# MainBoard.net
KiCad netlist of a schematic drawn in EAGLE
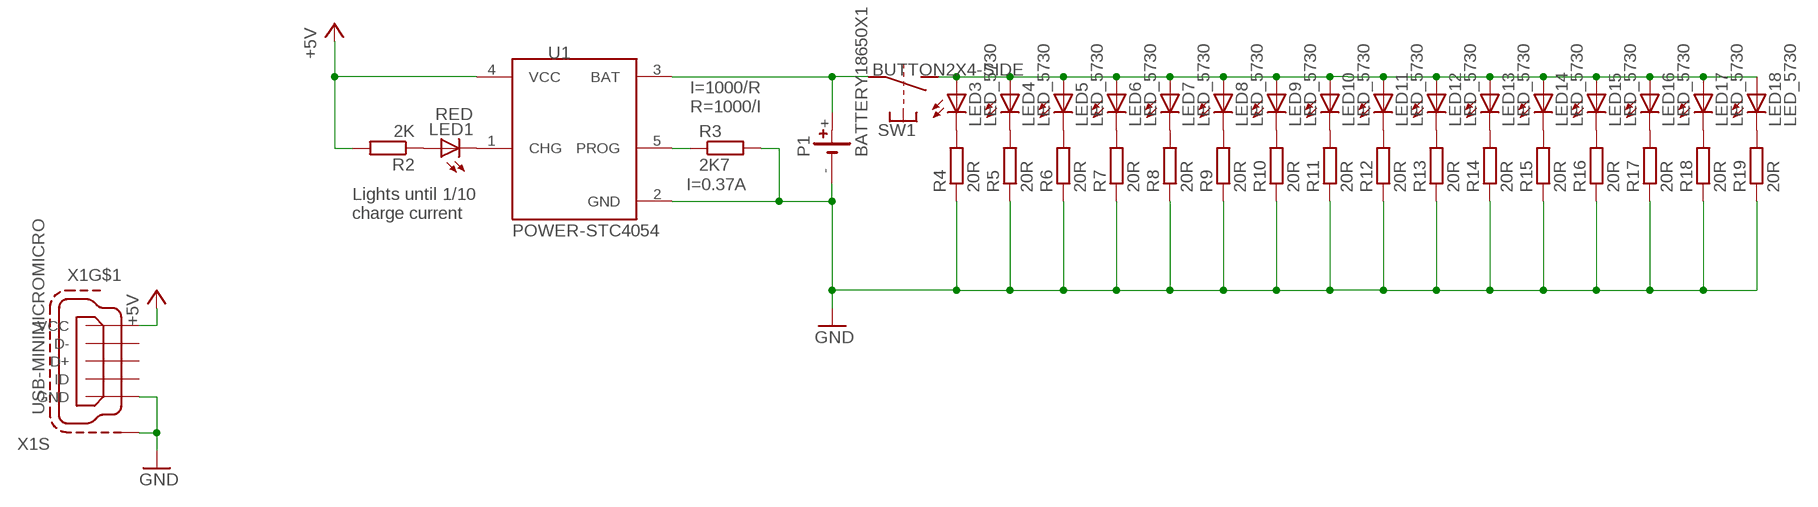
[diagram p0: schematic, sheet 1]

(export (version "E")
  (design (tool "Eeschema 10.0.6"))
  (components
    (comp (ref "LED1")
      (value "RED")
      (footprint "eagle-import:LED1206")
      (libsource (lib "eagle-import") (part "LED_1206"))
    )
    (comp (ref "LED3")
      (value "LED_5730")
      (footprint "eagle-import:LED5730")
      (libsource (lib "eagle-import") (part "LED_5730"))
    )
    (comp (ref "LED4")
      (value "LED_5730")
      (footprint "eagle-import:LED5730")
      (libsource (lib "eagle-import") (part "LED_5730"))
    )
    (comp (ref "LED5")
      (value "LED_5730")
      (footprint "eagle-import:LED5730")
      (libsource (lib "eagle-import") (part "LED_5730"))
    )
    (comp (ref "LED6")
      (value "LED_5730")
      (footprint "eagle-import:LED5730")
      (libsource (lib "eagle-import") (part "LED_5730"))
    )
    (comp (ref "LED7")
      (value "LED_5730")
      (footprint "eagle-import:LED5730")
      (libsource (lib "eagle-import") (part "LED_5730"))
    )
    (comp (ref "LED8")
      (value "LED_5730")
      (footprint "eagle-import:LED5730")
      (libsource (lib "eagle-import") (part "LED_5730"))
    )
    (comp (ref "LED9")
      (value "LED_5730")
      (footprint "eagle-import:LED5730")
      (libsource (lib "eagle-import") (part "LED_5730"))
    )
    (comp (ref "LED10")
      (value "LED_5730")
      (footprint "eagle-import:LED5730")
      (libsource (lib "eagle-import") (part "LED_5730"))
    )
    (comp (ref "LED11")
      (value "LED_5730")
      (footprint "eagle-import:LED5730")
      (libsource (lib "eagle-import") (part "LED_5730"))
    )
    (comp (ref "LED12")
      (value "LED_5730")
      (footprint "eagle-import:LED5730")
      (libsource (lib "eagle-import") (part "LED_5730"))
    )
    (comp (ref "LED13")
      (value "LED_5730")
      (footprint "eagle-import:LED5730")
      (libsource (lib "eagle-import") (part "LED_5730"))
    )
    (comp (ref "LED14")
      (value "LED_5730")
      (footprint "eagle-import:LED5730")
      (libsource (lib "eagle-import") (part "LED_5730"))
    )
    (comp (ref "LED15")
      (value "LED_5730")
      (footprint "eagle-import:LED5730")
      (libsource (lib "eagle-import") (part "LED_5730"))
    )
    (comp (ref "LED16")
      (value "LED_5730")
      (footprint "eagle-import:LED5730")
      (libsource (lib "eagle-import") (part "LED_5730"))
    )
    (comp (ref "LED17")
      (value "LED_5730")
      (footprint "eagle-import:LED5730")
      (libsource (lib "eagle-import") (part "LED_5730"))
    )
    (comp (ref "LED18")
      (value "LED_5730")
      (footprint "eagle-import:LED5730")
      (libsource (lib "eagle-import") (part "LED_5730"))
    )
    (comp (ref "P1")
      (value "BATTERY18650X1")
      (footprint "eagle-import:18650X1_HOLDER")
      (libsource (lib "eagle-import") (part "BATTERY18650X1"))
    )
    (comp (ref "R2")
      (value "2K")
      (footprint "eagle-import:RESC2012X50")
      (libsource (lib "eagle-import") (part "R_R0805"))
    )
    (comp (ref "R3")
      (value "2K7")
      (footprint "eagle-import:RESC2012X50")
      (libsource (lib "eagle-import") (part "R_R0805"))
    )
    (comp (ref "R4")
      (value "20R")
      (footprint "eagle-import:RESC2012X50")
      (libsource (lib "eagle-import") (part "R_R0805"))
    )
    (comp (ref "R5")
      (value "20R")
      (footprint "eagle-import:RESC2012X50")
      (libsource (lib "eagle-import") (part "R_R0805"))
    )
    (comp (ref "R6")
      (value "20R")
      (footprint "eagle-import:RESC2012X50")
      (libsource (lib "eagle-import") (part "R_R0805"))
    )
    (comp (ref "R7")
      (value "20R")
      (footprint "eagle-import:RESC2012X50")
      (libsource (lib "eagle-import") (part "R_R0805"))
    )
    (comp (ref "R8")
      (value "20R")
      (footprint "eagle-import:RESC2012X50")
      (libsource (lib "eagle-import") (part "R_R0805"))
    )
    (comp (ref "R9")
      (value "20R")
      (footprint "eagle-import:RESC2012X50")
      (libsource (lib "eagle-import") (part "R_R0805"))
    )
    (comp (ref "R10")
      (value "20R")
      (footprint "eagle-import:RESC2012X50")
      (libsource (lib "eagle-import") (part "R_R0805"))
    )
    (comp (ref "R11")
      (value "20R")
      (footprint "eagle-import:RESC2012X50")
      (libsource (lib "eagle-import") (part "R_R0805"))
    )
    (comp (ref "R12")
      (value "20R")
      (footprint "eagle-import:RESC2012X50")
      (libsource (lib "eagle-import") (part "R_R0805"))
    )
    (comp (ref "R13")
      (value "20R")
      (footprint "eagle-import:RESC2012X50")
      (libsource (lib "eagle-import") (part "R_R0805"))
    )
    (comp (ref "R14")
      (value "20R")
      (footprint "eagle-import:RESC2012X50")
      (libsource (lib "eagle-import") (part "R_R0805"))
    )
    (comp (ref "R15")
      (value "20R")
      (footprint "eagle-import:RESC2012X50")
      (libsource (lib "eagle-import") (part "R_R0805"))
    )
    (comp (ref "R16")
      (value "20R")
      (footprint "eagle-import:RESC2012X50")
      (libsource (lib "eagle-import") (part "R_R0805"))
    )
    (comp (ref "R17")
      (value "20R")
      (footprint "eagle-import:RESC2012X50")
      (libsource (lib "eagle-import") (part "R_R0805"))
    )
    (comp (ref "R18")
      (value "20R")
      (footprint "eagle-import:RESC2012X50")
      (libsource (lib "eagle-import") (part "R_R0805"))
    )
    (comp (ref "R19")
      (value "20R")
      (footprint "eagle-import:RESC2012X50")
      (libsource (lib "eagle-import") (part "R_R0805"))
    )
    (comp (ref "SW1")
      (value "BUTTON2X4-SIDE")
      (footprint "eagle-import:SW-2X4-SIDE")
      (libsource (lib "eagle-import") (part "BUTTON2X4-SIDE"))
    )
    (comp (ref "U1")
      (value "POWER-STC4054")
      (footprint "eagle-import:SOT95P280X145-5")
      (libsource (lib "eagle-import") (part "POWER-STC4054"))
    )
    (comp (ref "X1")
      (value "USB-MINIMICROMICRO")
      (footprint "eagle-import:USB-B-MICRO-SMD")
      (libsource (lib "eagle-import") (part "USB-MINIMICROMICRO"))
    )
  )
  (nets
    (net (code "1") (name "+5V") (class "Default")
      (node (ref "R2") (pin "2") (pinfunction "2_2") (pintype "passive"))
      (node (ref "U1") (pin "4") (pinfunction "VCC_4") (pintype "power_in"))
      (node (ref "X1") (pin "VBUS") (pinfunction "VCC_VBUS") (pintype "passive"))
    )
    (net (code "2") (name "GND") (class "Default")
      (node (ref "P1") (pin "-") (pinfunction "-_-") (pintype "passive"))
      (node (ref "R10") (pin "1") (pinfunction "1_1") (pintype "passive"))
      (node (ref "R11") (pin "1") (pinfunction "1_1") (pintype "passive"))
      (node (ref "R12") (pin "1") (pinfunction "1_1") (pintype "passive"))
      (node (ref "R13") (pin "1") (pinfunction "1_1") (pintype "passive"))
      (node (ref "R14") (pin "1") (pinfunction "1_1") (pintype "passive"))
      (node (ref "R15") (pin "1") (pinfunction "1_1") (pintype "passive"))
      (node (ref "R16") (pin "1") (pinfunction "1_1") (pintype "passive"))
      (node (ref "R17") (pin "1") (pinfunction "1_1") (pintype "passive"))
      (node (ref "R18") (pin "1") (pinfunction "1_1") (pintype "passive"))
      (node (ref "R19") (pin "1") (pinfunction "1_1") (pintype "passive"))
      (node (ref "R3") (pin "2") (pinfunction "2_2") (pintype "passive"))
      (node (ref "R4") (pin "1") (pinfunction "1_1") (pintype "passive"))
      (node (ref "R5") (pin "1") (pinfunction "1_1") (pintype "passive"))
      (node (ref "R6") (pin "1") (pinfunction "1_1") (pintype "passive"))
      (node (ref "R7") (pin "1") (pinfunction "1_1") (pintype "passive"))
      (node (ref "R8") (pin "1") (pinfunction "1_1") (pintype "passive"))
      (node (ref "R9") (pin "1") (pinfunction "1_1") (pintype "passive"))
      (node (ref "U1") (pin "2") (pinfunction "GND_2") (pintype "power_in"))
      (node (ref "X1") (pin "GND") (pinfunction "GND_GND") (pintype "passive"))
      (node (ref "X1") (pin "SHIELD1") (pinfunction "S1_SHIELD1") (pintype "passive"))
      (node (ref "X1") (pin "SHIELD2") (pinfunction "S1_SHIELD2") (pintype "passive"))
      (node (ref "X1") (pin "SHIELD3") (pinfunction "S1_SHIELD3") (pintype "passive"))
    )
    (net (code "3") (name "Net-(LED1-PadA)") (class "Default")
      (node (ref "LED1") (pin "A") (pinfunction "A_A") (pintype "passive"))
      (node (ref "R2") (pin "1") (pinfunction "1_1") (pintype "passive"))
    )
    (net (code "4") (name "Net-(LED3-PadC)") (class "Default")
      (node (ref "LED3") (pin "C") (pinfunction "C_C") (pintype "passive"))
      (node (ref "R4") (pin "2") (pinfunction "2_2") (pintype "passive"))
    )
    (net (code "5") (name "Net-(LED4-PadC)") (class "Default")
      (node (ref "LED4") (pin "C") (pinfunction "C_C") (pintype "passive"))
      (node (ref "R5") (pin "2") (pinfunction "2_2") (pintype "passive"))
    )
    (net (code "6") (name "Net-(LED5-PadC)") (class "Default")
      (node (ref "LED5") (pin "C") (pinfunction "C_C") (pintype "passive"))
      (node (ref "R6") (pin "2") (pinfunction "2_2") (pintype "passive"))
    )
    (net (code "7") (name "Net-(LED6-PadC)") (class "Default")
      (node (ref "LED6") (pin "C") (pinfunction "C_C") (pintype "passive"))
      (node (ref "R7") (pin "2") (pinfunction "2_2") (pintype "passive"))
    )
    (net (code "8") (name "Net-(LED7-PadC)") (class "Default")
      (node (ref "LED7") (pin "C") (pinfunction "C_C") (pintype "passive"))
      (node (ref "R8") (pin "2") (pinfunction "2_2") (pintype "passive"))
    )
    (net (code "9") (name "Net-(LED8-PadC)") (class "Default")
      (node (ref "LED8") (pin "C") (pinfunction "C_C") (pintype "passive"))
      (node (ref "R9") (pin "2") (pinfunction "2_2") (pintype "passive"))
    )
    (net (code "10") (name "Net-(LED9-PadC)") (class "Default")
      (node (ref "LED9") (pin "C") (pinfunction "C_C") (pintype "passive"))
      (node (ref "R10") (pin "2") (pinfunction "2_2") (pintype "passive"))
    )
    (net (code "11") (name "Net-(LED10-A-PadA1)") (class "Default")
      (node (ref "LED10") (pin "A") (pinfunction "A_A") (pintype "passive"))
      (node (ref "LED10") (pin "A1") (pinfunction "A_A1") (pintype "passive"))
      (node (ref "LED11") (pin "A") (pinfunction "A_A") (pintype "passive"))
      (node (ref "LED11") (pin "A1") (pinfunction "A_A1") (pintype "passive"))
      (node (ref "LED12") (pin "A") (pinfunction "A_A") (pintype "passive"))
      (node (ref "LED12") (pin "A1") (pinfunction "A_A1") (pintype "passive"))
      (node (ref "LED13") (pin "A") (pinfunction "A_A") (pintype "passive"))
      (node (ref "LED13") (pin "A1") (pinfunction "A_A1") (pintype "passive"))
      (node (ref "LED14") (pin "A") (pinfunction "A_A") (pintype "passive"))
      (node (ref "LED14") (pin "A1") (pinfunction "A_A1") (pintype "passive"))
      (node (ref "LED15") (pin "A") (pinfunction "A_A") (pintype "passive"))
      (node (ref "LED15") (pin "A1") (pinfunction "A_A1") (pintype "passive"))
      (node (ref "LED16") (pin "A") (pinfunction "A_A") (pintype "passive"))
      (node (ref "LED16") (pin "A1") (pinfunction "A_A1") (pintype "passive"))
      (node (ref "LED17") (pin "A") (pinfunction "A_A") (pintype "passive"))
      (node (ref "LED17") (pin "A1") (pinfunction "A_A1") (pintype "passive"))
      (node (ref "LED18") (pin "A") (pinfunction "A_A") (pintype "passive"))
      (node (ref "LED18") (pin "A1") (pinfunction "A_A1") (pintype "passive"))
      (node (ref "LED3") (pin "A") (pinfunction "A_A") (pintype "passive"))
      (node (ref "LED3") (pin "A1") (pinfunction "A_A1") (pintype "passive"))
      (node (ref "LED4") (pin "A") (pinfunction "A_A") (pintype "passive"))
      (node (ref "LED4") (pin "A1") (pinfunction "A_A1") (pintype "passive"))
      (node (ref "LED5") (pin "A") (pinfunction "A_A") (pintype "passive"))
      (node (ref "LED5") (pin "A1") (pinfunction "A_A1") (pintype "passive"))
      (node (ref "LED6") (pin "A") (pinfunction "A_A") (pintype "passive"))
      (node (ref "LED6") (pin "A1") (pinfunction "A_A1") (pintype "passive"))
      (node (ref "LED7") (pin "A") (pinfunction "A_A") (pintype "passive"))
      (node (ref "LED7") (pin "A1") (pinfunction "A_A1") (pintype "passive"))
      (node (ref "LED8") (pin "A") (pinfunction "A_A") (pintype "passive"))
      (node (ref "LED8") (pin "A1") (pinfunction "A_A1") (pintype "passive"))
      (node (ref "LED9") (pin "A") (pinfunction "A_A") (pintype "passive"))
      (node (ref "LED9") (pin "A1") (pinfunction "A_A1") (pintype "passive"))
      (node (ref "SW1") (pin "2") (pinfunction "2_2") (pintype "passive"))
    )
    (net (code "12") (name "Net-(LED10-PadC)") (class "Default")
      (node (ref "LED10") (pin "C") (pinfunction "C_C") (pintype "passive"))
      (node (ref "R11") (pin "2") (pinfunction "2_2") (pintype "passive"))
    )
    (net (code "13") (name "Net-(LED11-PadC)") (class "Default")
      (node (ref "LED11") (pin "C") (pinfunction "C_C") (pintype "passive"))
      (node (ref "R12") (pin "2") (pinfunction "2_2") (pintype "passive"))
    )
    (net (code "14") (name "Net-(LED12-PadC)") (class "Default")
      (node (ref "LED12") (pin "C") (pinfunction "C_C") (pintype "passive"))
      (node (ref "R13") (pin "2") (pinfunction "2_2") (pintype "passive"))
    )
    (net (code "15") (name "Net-(LED13-PadC)") (class "Default")
      (node (ref "LED13") (pin "C") (pinfunction "C_C") (pintype "passive"))
      (node (ref "R14") (pin "2") (pinfunction "2_2") (pintype "passive"))
    )
    (net (code "16") (name "Net-(LED14-PadC)") (class "Default")
      (node (ref "LED14") (pin "C") (pinfunction "C_C") (pintype "passive"))
      (node (ref "R15") (pin "2") (pinfunction "2_2") (pintype "passive"))
    )
    (net (code "17") (name "Net-(LED15-PadC)") (class "Default")
      (node (ref "LED15") (pin "C") (pinfunction "C_C") (pintype "passive"))
      (node (ref "R16") (pin "2") (pinfunction "2_2") (pintype "passive"))
    )
    (net (code "18") (name "Net-(LED16-PadC)") (class "Default")
      (node (ref "LED16") (pin "C") (pinfunction "C_C") (pintype "passive"))
      (node (ref "R17") (pin "2") (pinfunction "2_2") (pintype "passive"))
    )
    (net (code "19") (name "Net-(LED17-PadC)") (class "Default")
      (node (ref "LED17") (pin "C") (pinfunction "C_C") (pintype "passive"))
      (node (ref "R18") (pin "2") (pinfunction "2_2") (pintype "passive"))
    )
    (net (code "20") (name "Net-(LED18-PadC)") (class "Default")
      (node (ref "LED18") (pin "C") (pinfunction "C_C") (pintype "passive"))
      (node (ref "R19") (pin "2") (pinfunction "2_2") (pintype "passive"))
    )
    (net (code "21") (name "Net-(U1-BAT)") (class "Default")
      (node (ref "P1") (pin "+") (pinfunction "+_+") (pintype "passive"))
      (node (ref "SW1") (pin "1") (pinfunction "1_1") (pintype "passive"))
      (node (ref "U1") (pin "3") (pinfunction "BAT_3") (pintype "bidirectional"))
    )
    (net (code "22") (name "Net-(U1-CHG)") (class "Default")
      (node (ref "LED1") (pin "C") (pinfunction "C_C") (pintype "passive"))
      (node (ref "U1") (pin "1") (pinfunction "CHG_1") (pintype "output"))
    )
    (net (code "23") (name "Net-(U1-PROG)") (class "Default")
      (node (ref "R3") (pin "1") (pinfunction "1_1") (pintype "passive"))
      (node (ref "U1") (pin "5") (pinfunction "PROG_5") (pintype "bidirectional"))
    )
    (net (code "24") (name "unconnected-(X1-PadD+)") (class "Default")
      (node (ref "X1") (pin "D+") (pinfunction "D+_D+") (pintype "passive"))
    )
    (net (code "25") (name "unconnected-(X1-PadD-)") (class "Default")
      (node (ref "X1") (pin "D-") (pinfunction "D-_D-") (pintype "passive"))
    )
    (net (code "26") (name "unconnected-(X1-PadID)") (class "Default")
      (node (ref "X1") (pin "ID") (pinfunction "ID_ID") (pintype "passive"))
    )
  )
)
